# Iridium_Beacon_Radio_Board.net
KiCad netlist of a schematic drawn in EAGLE
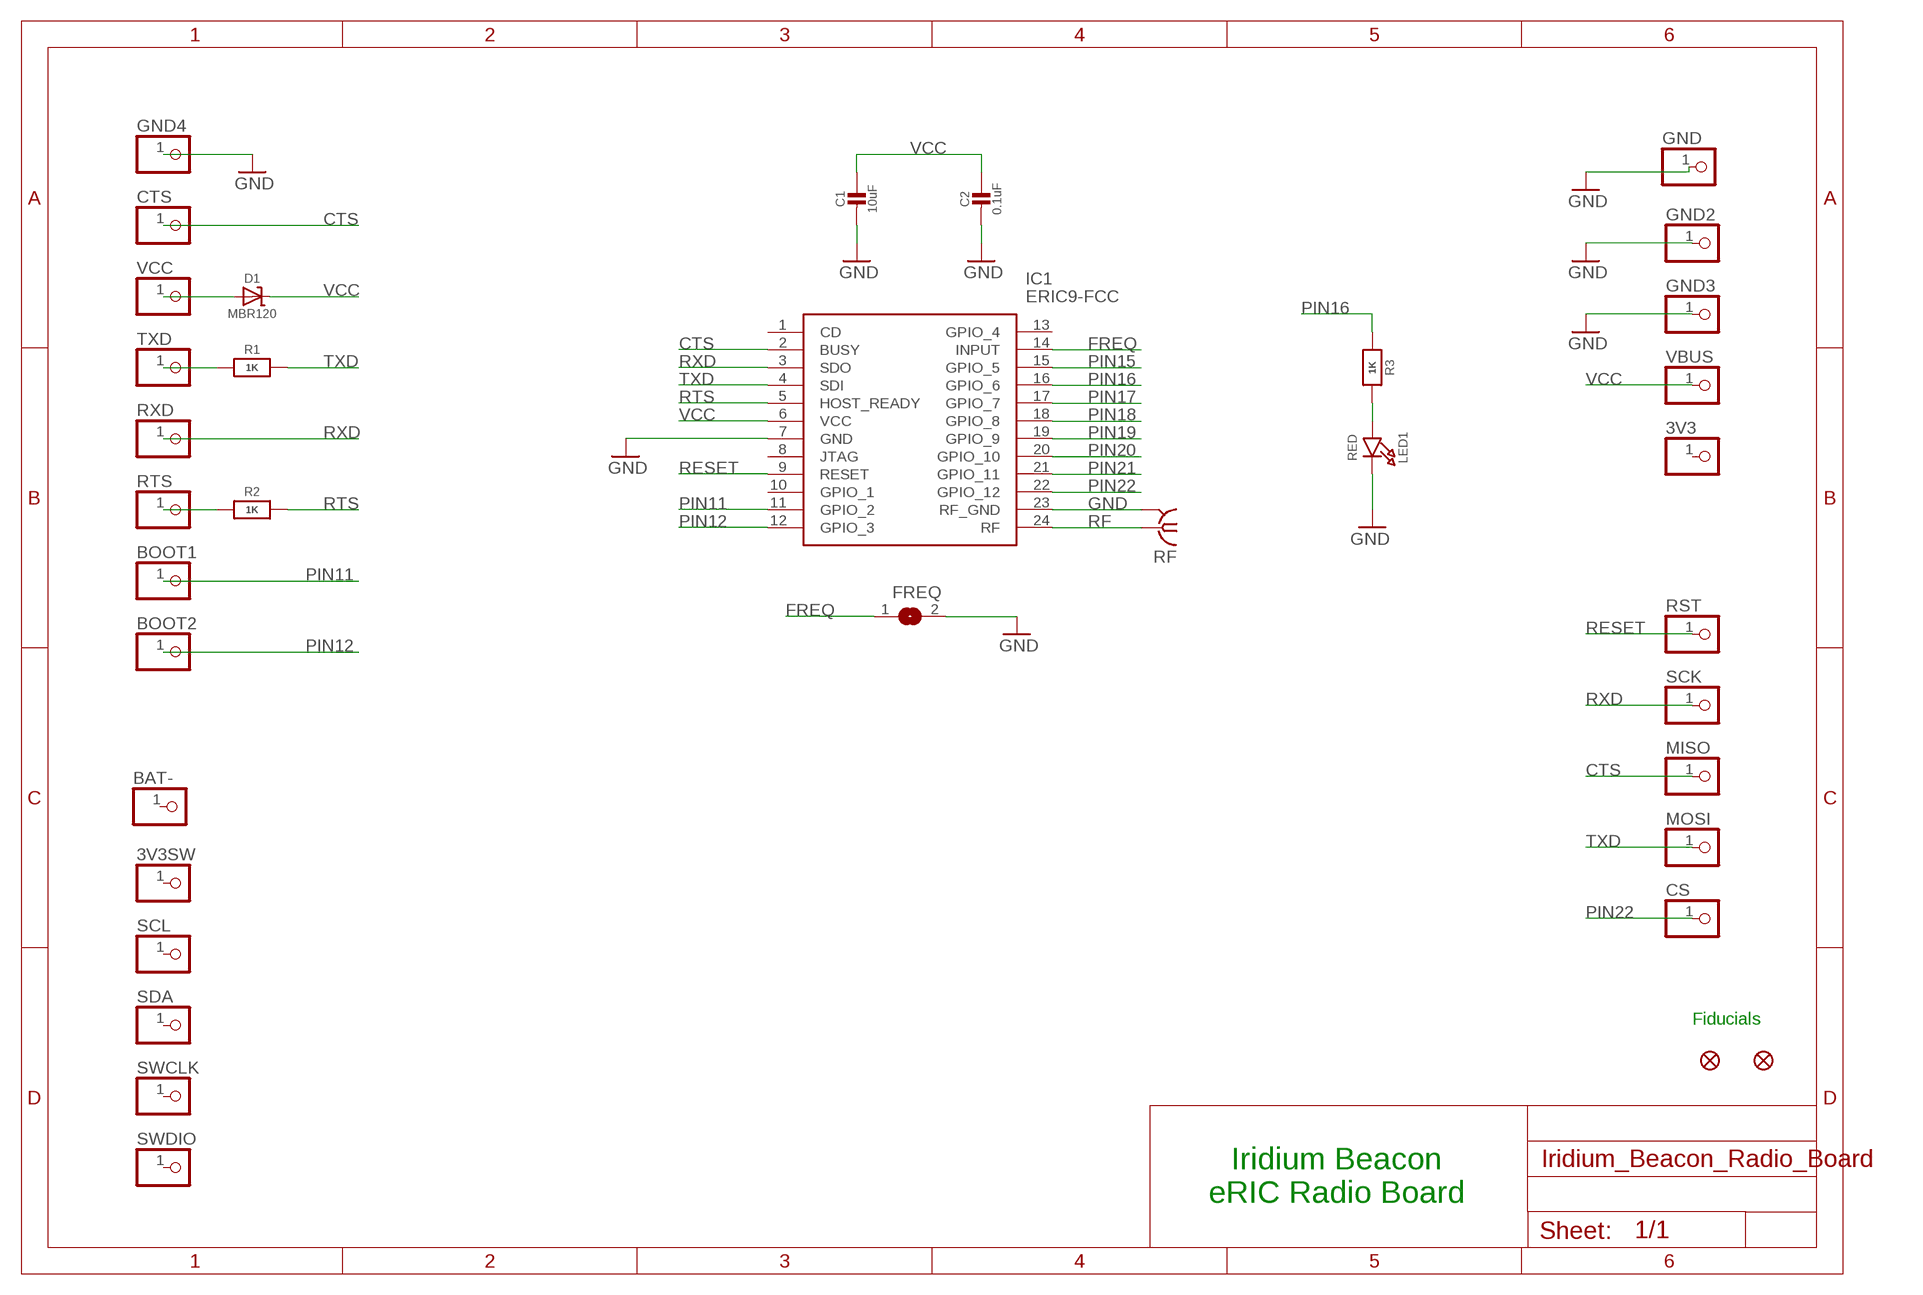
[diagram p0: schematic, sheet 1]

(export (version "E")
  (design (tool "Eeschema 10.0.6"))
  (components
    (comp (ref "3V3")
      (value "PINHD-1X1")
      (footprint "eagle-import:1X01")
      (libsource (lib "eagle-import") (part "PINHD-1X1"))
    )
    (comp (ref "3V3SW")
      (value "PINHD-1X1")
      (footprint "eagle-import:1X01")
      (libsource (lib "eagle-import") (part "PINHD-1X1"))
    )
    (comp (ref "BAT-")
      (value "PINHD-1X1")
      (footprint "eagle-import:1X01")
      (libsource (lib "eagle-import") (part "PINHD-1X1"))
    )
    (comp (ref "BOOT1")
      (value "PINHD-1X1")
      (footprint "eagle-import:1X01")
      (libsource (lib "eagle-import") (part "PINHD-1X1"))
    )
    (comp (ref "BOOT2")
      (value "PINHD-1X1")
      (footprint "eagle-import:1X01")
      (libsource (lib "eagle-import") (part "PINHD-1X1"))
    )
    (comp (ref "C1")
      (value "10uF")
      (footprint "eagle-import:0805-NO")
      (libsource (lib "eagle-import") (part "CAP_CERAMIC0805-NOOUTLINE"))
    )
    (comp (ref "C2")
      (value "0.1uF")
      (footprint "eagle-import:0603-NO")
      (libsource (lib "eagle-import") (part "CAP_CERAMIC0603_NO"))
    )
    (comp (ref "CS")
      (value "PINHD-1X1")
      (footprint "eagle-import:1X01")
      (libsource (lib "eagle-import") (part "PINHD-1X1"))
    )
    (comp (ref "CTS")
      (value "PINHD-1X1")
      (footprint "eagle-import:1X01")
      (libsource (lib "eagle-import") (part "PINHD-1X1"))
    )
    (comp (ref "D1")
      (value "MBR120")
      (footprint "eagle-import:SOD-123")
      (libsource (lib "eagle-import") (part "DIODE-SCHOTTKYSOD-123"))
    )
    (comp (ref "FD1")
      (value "FIDUCIAL1X2")
      (footprint "eagle-import:FIDUCIAL-1X2")
      (libsource (lib "eagle-import") (part "FIDUCIAL1X2"))
    )
    (comp (ref "FD2")
      (value "FIDUCIAL1X2")
      (footprint "eagle-import:FIDUCIAL-1X2")
      (libsource (lib "eagle-import") (part "FIDUCIAL1X2"))
    )
    (comp (ref "FREQ")
      (value "SOLDERJUMPER")
      (footprint "eagle-import:SOLDERJUMPER_ARROW_NOPASTE")
      (libsource (lib "eagle-import") (part "SOLDERJUMPER"))
    )
    (comp (ref "GND")
      (value "PINHD-1X1")
      (footprint "eagle-import:1X01")
      (libsource (lib "eagle-import") (part "PINHD-1X1"))
    )
    (comp (ref "GND2")
      (value "PINHD-1X1")
      (footprint "eagle-import:1X01")
      (libsource (lib "eagle-import") (part "PINHD-1X1"))
    )
    (comp (ref "GND3")
      (value "PINHD-1X1")
      (footprint "eagle-import:1X01")
      (libsource (lib "eagle-import") (part "PINHD-1X1"))
    )
    (comp (ref "GND4")
      (value "PINHD-1X1")
      (footprint "eagle-import:1X01")
      (libsource (lib "eagle-import") (part "PINHD-1X1"))
    )
    (comp (ref "IC1")
      (value "ERIC9-FCC")
      (footprint "eagle-import:ERIC4")
      (fields (field (name "ARROW_PART_NUMBER") "eRIC9-FCC"))
      (libsource (lib "eagle-import") (part "ERIC9-FCC"))
    )
    (comp (ref "LED1")
      (value "RED")
      (footprint "eagle-import:CHIPLED_0805_NOOUTLINE")
      (libsource (lib "eagle-import") (part "LED0805_NOOUTLINE"))
    )
    (comp (ref "MISO")
      (value "PINHD-1X1")
      (footprint "eagle-import:1X01")
      (libsource (lib "eagle-import") (part "PINHD-1X1"))
    )
    (comp (ref "MOSI")
      (value "PINHD-1X1")
      (footprint "eagle-import:1X01")
      (libsource (lib "eagle-import") (part "PINHD-1X1"))
    )
    (comp (ref "R1")
      (value "1K")
      (footprint "eagle-import:0603-NO")
      (libsource (lib "eagle-import") (part "RESISTOR_0603_NOOUT"))
    )
    (comp (ref "R2")
      (value "1K")
      (footprint "eagle-import:0603-NO")
      (libsource (lib "eagle-import") (part "RESISTOR_0603_NOOUT"))
    )
    (comp (ref "R3")
      (value "1K")
      (footprint "eagle-import:0603-NO")
      (libsource (lib "eagle-import") (part "RESISTOR_0603_NOOUT"))
    )
    (comp (ref "RF")
      (value "SMA-142-0711-821/826")
      (footprint "eagle-import:J502-ND-142-0711-821_826")
      (fields (field (name "MF") "JOHNSON COMPONENTS") (field (name "MPN") "142-0711-821"))
      (libsource (lib "eagle-import") (part "SMA-142-0711-821/826"))
    )
    (comp (ref "RST")
      (value "PINHD-1X1")
      (footprint "eagle-import:1X01")
      (libsource (lib "eagle-import") (part "PINHD-1X1"))
    )
    (comp (ref "RTS")
      (value "PINHD-1X1")
      (footprint "eagle-import:1X01")
      (libsource (lib "eagle-import") (part "PINHD-1X1"))
    )
    (comp (ref "RXD")
      (value "PINHD-1X1")
      (footprint "eagle-import:1X01")
      (libsource (lib "eagle-import") (part "PINHD-1X1"))
    )
    (comp (ref "SCK")
      (value "PINHD-1X1")
      (footprint "eagle-import:1X01")
      (libsource (lib "eagle-import") (part "PINHD-1X1"))
    )
    (comp (ref "SCL")
      (value "PINHD-1X1")
      (footprint "eagle-import:1X01")
      (libsource (lib "eagle-import") (part "PINHD-1X1"))
    )
    (comp (ref "SDA")
      (value "PINHD-1X1")
      (footprint "eagle-import:1X01")
      (libsource (lib "eagle-import") (part "PINHD-1X1"))
    )
    (comp (ref "SWCLK")
      (value "PINHD-1X1")
      (footprint "eagle-import:1X01")
      (libsource (lib "eagle-import") (part "PINHD-1X1"))
    )
    (comp (ref "SWDIO")
      (value "PINHD-1X1")
      (footprint "eagle-import:1X01")
      (libsource (lib "eagle-import") (part "PINHD-1X1"))
    )
    (comp (ref "TXD")
      (value "PINHD-1X1")
      (footprint "eagle-import:1X01")
      (libsource (lib "eagle-import") (part "PINHD-1X1"))
    )
    (comp (ref "VBUS")
      (value "PINHD-1X1")
      (footprint "eagle-import:1X01")
      (libsource (lib "eagle-import") (part "PINHD-1X1"))
    )
    (comp (ref "VCC")
      (value "PINHD-1X1")
      (footprint "eagle-import:1X01")
      (libsource (lib "eagle-import") (part "PINHD-1X1"))
    )
  )
  (nets
    (net (code "1") (name "/CTS") (class "Default")
      (node (ref "CTS") (pin "1") (pinfunction "1_1") (pintype "passive"))
      (node (ref "IC1") (pin "2") (pinfunction "BUSY_2") (pintype "bidirectional"))
      (node (ref "MISO") (pin "1") (pinfunction "1_1") (pintype "passive"))
    )
    (net (code "2") (name "/FREQ") (class "Default")
      (node (ref "FREQ") (pin "1") (pinfunction "1_1") (pintype "passive"))
      (node (ref "IC1") (pin "14") (pinfunction "INPUT_14") (pintype "bidirectional"))
    )
    (net (code "3") (name "/PIN11") (class "Default")
      (node (ref "BOOT1") (pin "1") (pinfunction "1_1") (pintype "passive"))
      (node (ref "IC1") (pin "11") (pinfunction "GPIO_2_11") (pintype "bidirectional"))
    )
    (net (code "4") (name "/PIN12") (class "Default")
      (node (ref "BOOT2") (pin "1") (pinfunction "1_1") (pintype "passive"))
      (node (ref "IC1") (pin "12") (pinfunction "GPIO_3_12") (pintype "bidirectional"))
    )
    (net (code "5") (name "/PIN15") (class "Default")
      (node (ref "IC1") (pin "15") (pinfunction "GPIO_5_15") (pintype "bidirectional"))
    )
    (net (code "6") (name "/PIN16") (class "Default")
      (node (ref "IC1") (pin "16") (pinfunction "GPIO_6_16") (pintype "bidirectional"))
      (node (ref "R3") (pin "1") (pinfunction "1_1") (pintype "passive"))
    )
    (net (code "7") (name "/PIN17") (class "Default")
      (node (ref "IC1") (pin "17") (pinfunction "GPIO_7_17") (pintype "bidirectional"))
    )
    (net (code "8") (name "/PIN18") (class "Default")
      (node (ref "IC1") (pin "18") (pinfunction "GPIO_8_18") (pintype "bidirectional"))
    )
    (net (code "9") (name "/PIN19") (class "Default")
      (node (ref "IC1") (pin "19") (pinfunction "GPIO_9_19") (pintype "bidirectional"))
    )
    (net (code "10") (name "/PIN20") (class "Default")
      (node (ref "IC1") (pin "20") (pinfunction "GPIO_10_20") (pintype "bidirectional"))
    )
    (net (code "11") (name "/PIN21") (class "Default")
      (node (ref "IC1") (pin "21") (pinfunction "GPIO_11_21") (pintype "bidirectional"))
    )
    (net (code "12") (name "/PIN22") (class "Default")
      (node (ref "CS") (pin "1") (pinfunction "1_1") (pintype "passive"))
      (node (ref "IC1") (pin "22") (pinfunction "GPIO_12_22") (pintype "bidirectional"))
    )
    (net (code "13") (name "/RESET") (class "Default")
      (node (ref "IC1") (pin "9") (pinfunction "RESET_9") (pintype "bidirectional"))
      (node (ref "RST") (pin "1") (pinfunction "1_1") (pintype "passive"))
    )
    (net (code "14") (name "/RF") (class "Default")
      (node (ref "IC1") (pin "24") (pinfunction "RF_24") (pintype "bidirectional"))
      (node (ref "RF") (pin "1") (pinfunction "1_1") (pintype "passive"))
    )
    (net (code "15") (name "/RTS") (class "Default")
      (node (ref "IC1") (pin "5") (pinfunction "HOST_READY_5") (pintype "bidirectional"))
      (node (ref "R2") (pin "2") (pinfunction "2_2") (pintype "passive"))
    )
    (net (code "16") (name "/RXD") (class "Default")
      (node (ref "IC1") (pin "3") (pinfunction "SDO_3") (pintype "bidirectional"))
      (node (ref "RXD") (pin "1") (pinfunction "1_1") (pintype "passive"))
      (node (ref "SCK") (pin "1") (pinfunction "1_1") (pintype "passive"))
    )
    (net (code "17") (name "/TXD") (class "Default")
      (node (ref "IC1") (pin "4") (pinfunction "SDI_4") (pintype "bidirectional"))
      (node (ref "MOSI") (pin "1") (pinfunction "1_1") (pintype "passive"))
      (node (ref "R1") (pin "2") (pinfunction "2_2") (pintype "passive"))
    )
    (net (code "18") (name "/VCC") (class "Default")
      (node (ref "C1") (pin "1") (pinfunction "1_1") (pintype "passive"))
      (node (ref "C2") (pin "1") (pinfunction "1_1") (pintype "passive"))
      (node (ref "D1") (pin "C") (pinfunction "C_C") (pintype "passive"))
      (node (ref "IC1") (pin "6") (pinfunction "VCC_6") (pintype "bidirectional"))
      (node (ref "VBUS") (pin "1") (pinfunction "1_1") (pintype "passive"))
    )
    (net (code "19") (name "GND") (class "Default")
      (node (ref "C1") (pin "2") (pinfunction "2_2") (pintype "passive"))
      (node (ref "C2") (pin "2") (pinfunction "2_2") (pintype "passive"))
      (node (ref "FREQ") (pin "2") (pinfunction "2_2") (pintype "passive"))
      (node (ref "GND") (pin "1") (pinfunction "1_1") (pintype "passive"))
      (node (ref "GND2") (pin "1") (pinfunction "1_1") (pintype "passive"))
      (node (ref "GND3") (pin "1") (pinfunction "1_1") (pintype "passive"))
      (node (ref "GND4") (pin "1") (pinfunction "1_1") (pintype "passive"))
      (node (ref "IC1") (pin "23") (pinfunction "RF_GND_23") (pintype "bidirectional"))
      (node (ref "IC1") (pin "7") (pinfunction "GND_7") (pintype "bidirectional"))
      (node (ref "LED1") (pin "C") (pinfunction "C_C") (pintype "passive"))
      (node (ref "RF") (pin "G@1") (pinfunction "2_G@1") (pintype "passive"))
      (node (ref "RF") (pin "G@2") (pinfunction "2_G@2") (pintype "passive"))
      (node (ref "RF") (pin "G@3") (pinfunction "2_G@3") (pintype "passive"))
      (node (ref "RF") (pin "G@4") (pinfunction "2_G@4") (pintype "passive"))
    )
    (net (code "20") (name "Net-(D1-PadA)") (class "Default")
      (node (ref "D1") (pin "A") (pinfunction "A_A") (pintype "passive"))
      (node (ref "VCC") (pin "1") (pinfunction "1_1") (pintype "passive"))
    )
    (net (code "21") (name "Net-(LED1-PadA)") (class "Default")
      (node (ref "LED1") (pin "A") (pinfunction "A_A") (pintype "passive"))
      (node (ref "R3") (pin "2") (pinfunction "2_2") (pintype "passive"))
    )
    (net (code "22") (name "Net-(R1-Pad1)") (class "Default")
      (node (ref "R1") (pin "1") (pinfunction "1_1") (pintype "passive"))
      (node (ref "TXD") (pin "1") (pinfunction "1_1") (pintype "passive"))
    )
    (net (code "23") (name "Net-(R2-Pad1)") (class "Default")
      (node (ref "R2") (pin "1") (pinfunction "1_1") (pintype "passive"))
      (node (ref "RTS") (pin "1") (pinfunction "1_1") (pintype "passive"))
    )
    (net (code "24") (name "unconnected-(3V3-Pad1)") (class "Default")
      (node (ref "3V3") (pin "1") (pinfunction "1_1") (pintype "passive"))
    )
    (net (code "25") (name "unconnected-(3V3SW-Pad1)") (class "Default")
      (node (ref "3V3SW") (pin "1") (pinfunction "1_1") (pintype "passive"))
    )
    (net (code "26") (name "unconnected-(BAT--Pad1)") (class "Default")
      (node (ref "BAT-") (pin "1") (pinfunction "1_1") (pintype "passive"))
    )
    (net (code "27") (name "unconnected-(IC1-CD-Pad1)") (class "Default")
      (node (ref "IC1") (pin "1") (pinfunction "CD_1") (pintype "bidirectional"))
    )
    (net (code "28") (name "unconnected-(IC1-GPIO_1-Pad10)") (class "Default")
      (node (ref "IC1") (pin "10") (pinfunction "GPIO_1_10") (pintype "bidirectional"))
    )
    (net (code "29") (name "unconnected-(IC1-GPIO_4-Pad13)") (class "Default")
      (node (ref "IC1") (pin "13") (pinfunction "GPIO_4_13") (pintype "bidirectional"))
    )
    (net (code "30") (name "unconnected-(IC1-JTAG-Pad8)") (class "Default")
      (node (ref "IC1") (pin "8") (pinfunction "JTAG_8") (pintype "bidirectional"))
    )
    (net (code "31") (name "unconnected-(SCL-Pad1)") (class "Default")
      (node (ref "SCL") (pin "1") (pinfunction "1_1") (pintype "passive"))
    )
    (net (code "32") (name "unconnected-(SDA-Pad1)") (class "Default")
      (node (ref "SDA") (pin "1") (pinfunction "1_1") (pintype "passive"))
    )
    (net (code "33") (name "unconnected-(SWCLK-Pad1)") (class "Default")
      (node (ref "SWCLK") (pin "1") (pinfunction "1_1") (pintype "passive"))
    )
    (net (code "34") (name "unconnected-(SWDIO-Pad1)") (class "Default")
      (node (ref "SWDIO") (pin "1") (pinfunction "1_1") (pintype "passive"))
    )
  )
)
